# 18250_0.net
KiCad netlist of a schematic drawn in EAGLE
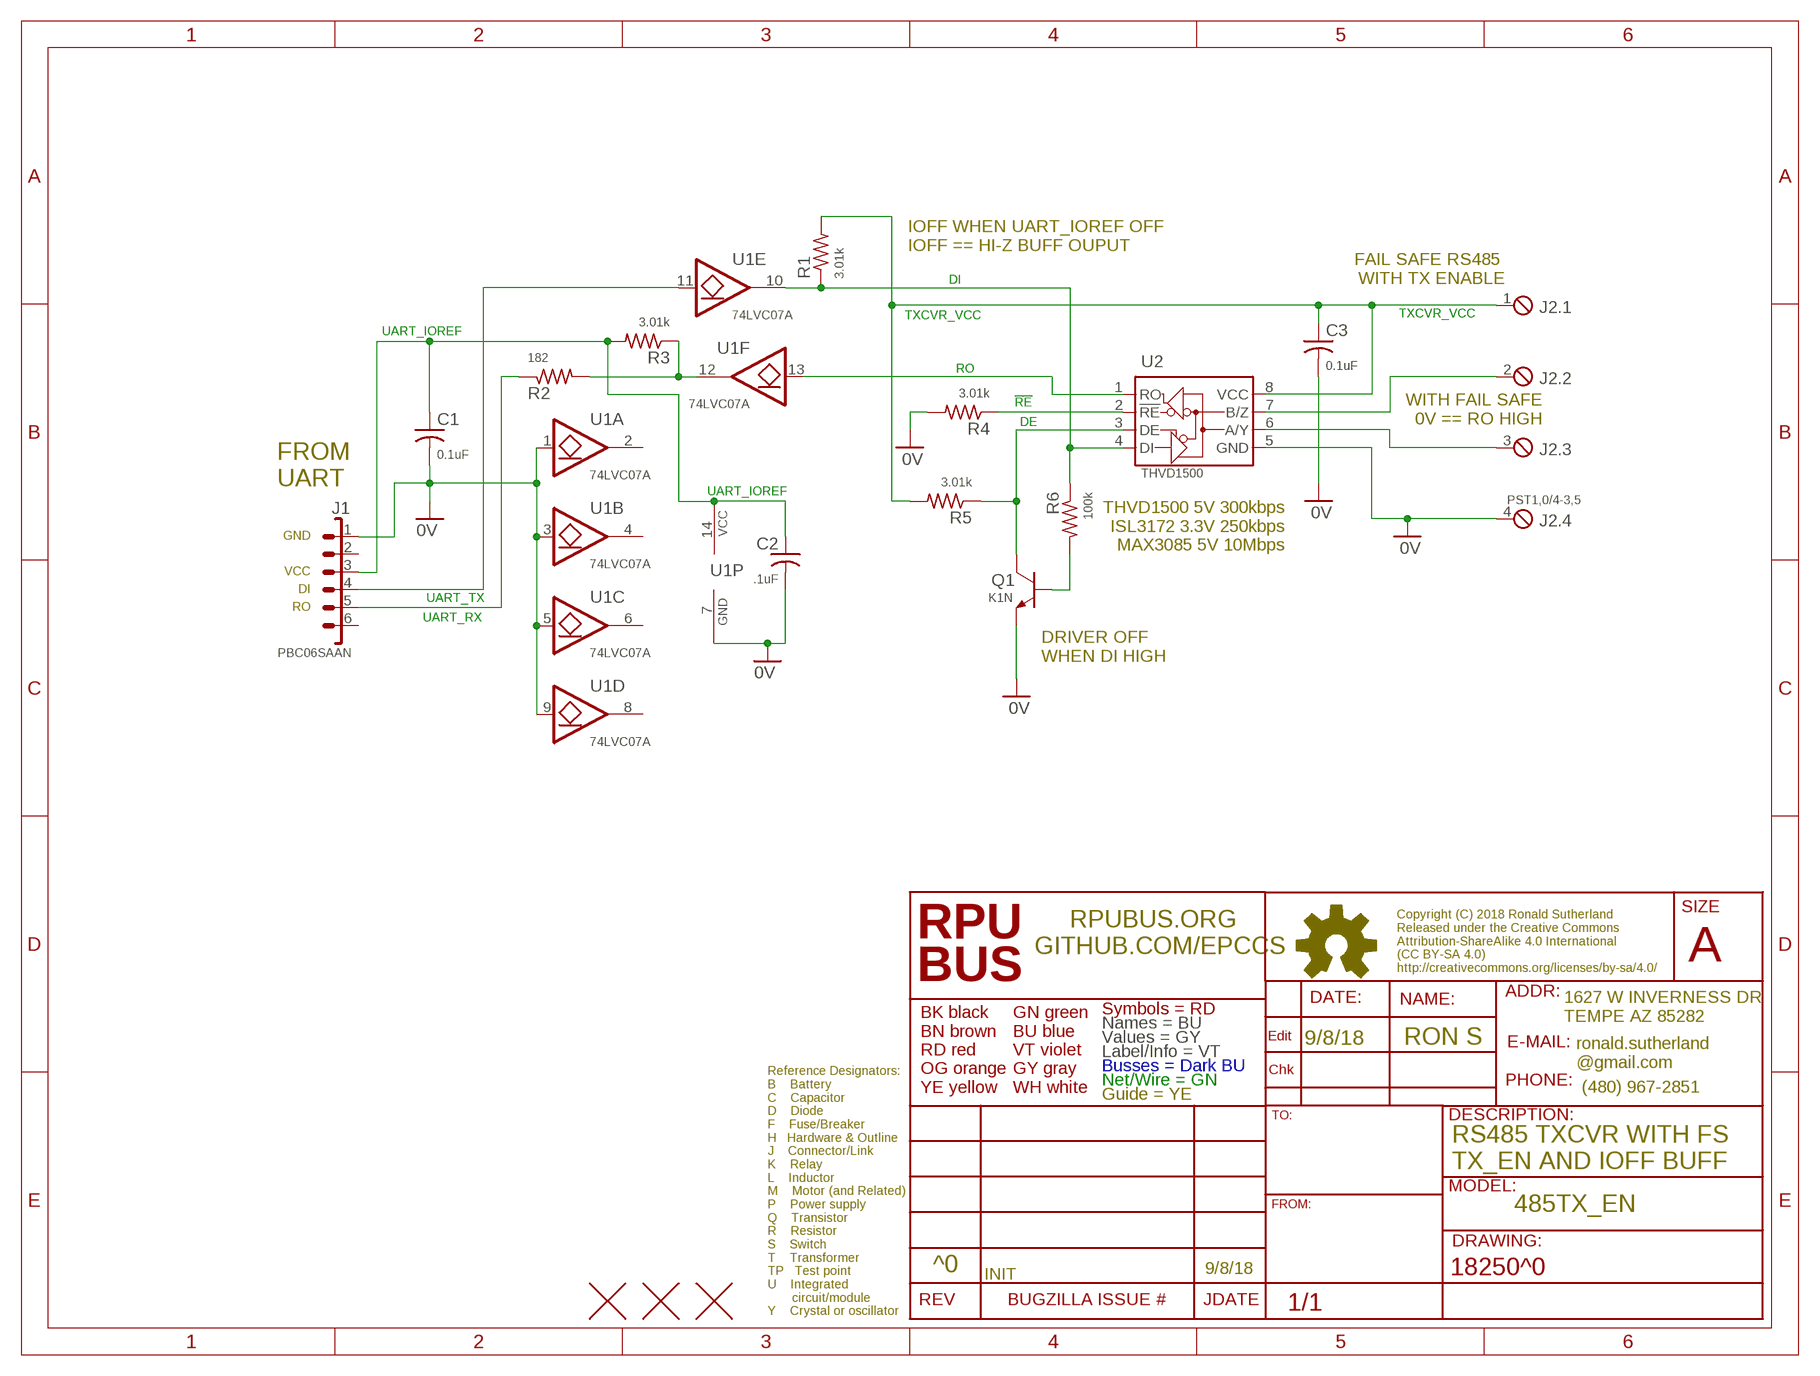
[diagram p0: schematic, sheet 1]

(export (version "E")
  (design (tool "Eeschema 10.0.6"))
  (components
    (comp (ref "C1")
      (value "0.1uF")
      (footprint "eagle-import:C0603(1608)")
      (libsource (lib "eagle-import") (part "CC0603A"))
    )
    (comp (ref "C2")
      (value ".1uF")
      (footprint "eagle-import:C0603(1608)")
      (libsource (lib "eagle-import") (part "CC0603A"))
    )
    (comp (ref "C3")
      (value "0.1uF")
      (footprint "eagle-import:C0603(1608)")
      (libsource (lib "eagle-import") (part "CC0603A"))
    )
    (comp (ref "J1")
      (value "PBC06SAAN")
      (footprint "eagle-import:1X6")
      (libsource (lib "eagle-import") (part "1X6"))
    )
    (comp (ref "J2")
      (value "PST1,0/4-3,5")
      (footprint "eagle-import:MCV4")
      (libsource (lib "eagle-import") (part "MCV4"))
    )
    (comp (ref "Q1")
      (value "K1N")
      (footprint "eagle-import:SOT23")
      (libsource (lib "eagle-import") (part "NPNSOT23"))
    )
    (comp (ref "R1")
      (value "3.01k")
      (footprint "eagle-import:C0805(2012)")
      (libsource (lib "eagle-import") (part "R0805"))
    )
    (comp (ref "R2")
      (value "182")
      (footprint "eagle-import:C0805(2012)")
      (libsource (lib "eagle-import") (part "R0805"))
    )
    (comp (ref "R3")
      (value "3.01k")
      (footprint "eagle-import:C0805(2012)")
      (libsource (lib "eagle-import") (part "R0805"))
    )
    (comp (ref "R4")
      (value "3.01k")
      (footprint "eagle-import:C0805(2012)")
      (libsource (lib "eagle-import") (part "R0805"))
    )
    (comp (ref "R5")
      (value "3.01k")
      (footprint "eagle-import:C0805(2012)")
      (libsource (lib "eagle-import") (part "R0805"))
    )
    (comp (ref "R6")
      (value "100k")
      (footprint "eagle-import:C0805(2012)")
      (libsource (lib "eagle-import") (part "R0805"))
    )
    (comp (ref "U$2")
      (value "FIDUCIAL1.27")
      (footprint "eagle-import:FIDUCIAL-1.27")
      (libsource (lib "eagle-import") (part "FIDUCIAL1.27"))
    )
    (comp (ref "U$3")
      (value "FIDUCIAL1.27")
      (footprint "eagle-import:FIDUCIAL-1.27")
      (libsource (lib "eagle-import") (part "FIDUCIAL1.27"))
    )
    (comp (ref "U$4")
      (value "FIDUCIAL1.27")
      (footprint "eagle-import:FIDUCIAL-1.27")
      (libsource (lib "eagle-import") (part "FIDUCIAL1.27"))
    )
    (comp (ref "U1")
      (value "74LVC07A")
      (footprint "eagle-import:14SOIC")
      (libsource (lib "eagle-import") (part "7407D"))
    )
    (comp (ref "U2")
      (value "THVD1500")
      (footprint "eagle-import:SOIC8")
      (libsource (lib "eagle-import") (part "ISL3172EIBZ"))
    )
  )
  (nets
    (net (code "1") (name "/DE") (class "Default")
      (node (ref "Q1") (pin "C") (pinfunction "C_C") (pintype "passive"))
      (node (ref "R5") (pin "1") (pinfunction "1_1") (pintype "passive"))
      (node (ref "U2") (pin "3") (pinfunction "DE_3") (pintype "input"))
    )
    (net (code "2") (name "/DI") (class "Default")
      (node (ref "R1") (pin "1") (pinfunction "1_1") (pintype "passive"))
      (node (ref "R6") (pin "1") (pinfunction "1_1") (pintype "passive"))
      (node (ref "U1") (pin "10") (pinfunction "O_10") (pintype "open_collector"))
      (node (ref "U2") (pin "4") (pinfunction "DI_4") (pintype "input"))
    )
    (net (code "3") (name "/RO") (class "Default")
      (node (ref "U1") (pin "13") (pinfunction "I_13") (pintype "input"))
      (node (ref "U2") (pin "1") (pinfunction "RO_1") (pintype "output"))
    )
    (net (code "4") (name "/TXCVR_VCC") (class "Default")
      (node (ref "C3") (pin "1") (pinfunction "1_1") (pintype "passive"))
      (node (ref "J2") (pin "1") (pinfunction "1_1") (pintype "passive"))
      (node (ref "R1") (pin "2") (pinfunction "2_2") (pintype "passive"))
      (node (ref "R5") (pin "2") (pinfunction "2_2") (pintype "passive"))
      (node (ref "U2") (pin "8") (pinfunction "VCC_8") (pintype "power_in"))
    )
    (net (code "5") (name "/UART_IOREF") (class "Default")
      (node (ref "C1") (pin "1") (pinfunction "1_1") (pintype "passive"))
      (node (ref "C2") (pin "1") (pinfunction "1_1") (pintype "passive"))
      (node (ref "J1") (pin "3") (pinfunction "3_3") (pintype "passive"))
      (node (ref "R3") (pin "2") (pinfunction "2_2") (pintype "passive"))
      (node (ref "U1") (pin "14") (pinfunction "VCC_14") (pintype "power_in"))
    )
    (net (code "6") (name "/UART_RX") (class "Default")
      (node (ref "J1") (pin "5") (pinfunction "5_5") (pintype "passive"))
      (node (ref "R2") (pin "1") (pinfunction "1_1") (pintype "passive"))
    )
    (net (code "7") (name "/UART_TX") (class "Default")
      (node (ref "J1") (pin "4") (pinfunction "4_4") (pintype "passive"))
      (node (ref "U1") (pin "11") (pinfunction "I_11") (pintype "input"))
    )
    (net (code "8") (name "/~{RE}") (class "Default")
      (node (ref "R4") (pin "1") (pinfunction "1_1") (pintype "passive"))
      (node (ref "U2") (pin "2") (pinfunction "~{RE}_2") (pintype "input"))
    )
    (net (code "9") (name "0V") (class "Default")
      (node (ref "C1") (pin "2") (pinfunction "2_2") (pintype "passive"))
      (node (ref "C2") (pin "2") (pinfunction "2_2") (pintype "passive"))
      (node (ref "C3") (pin "2") (pinfunction "2_2") (pintype "passive"))
      (node (ref "J1") (pin "1") (pinfunction "1_1") (pintype "passive"))
      (node (ref "J2") (pin "4") (pinfunction "1_4") (pintype "passive"))
      (node (ref "Q1") (pin "E") (pinfunction "E_E") (pintype "passive"))
      (node (ref "R4") (pin "2") (pinfunction "2_2") (pintype "passive"))
      (node (ref "U1") (pin "1") (pinfunction "I_1") (pintype "input"))
      (node (ref "U1") (pin "3") (pinfunction "I_3") (pintype "input"))
      (node (ref "U1") (pin "5") (pinfunction "I_5") (pintype "input"))
      (node (ref "U1") (pin "7") (pinfunction "GND_7") (pintype "power_in"))
      (node (ref "U1") (pin "9") (pinfunction "I_9") (pintype "input"))
      (node (ref "U2") (pin "5") (pinfunction "GND_5") (pintype "power_in"))
    )
    (net (code "10") (name "Net-(J2B-1)") (class "Default")
      (node (ref "J2") (pin "2") (pinfunction "1_2") (pintype "passive"))
      (node (ref "U2") (pin "7") (pinfunction "B/Z_7") (pintype "bidirectional"))
    )
    (net (code "11") (name "Net-(J2C-1)") (class "Default")
      (node (ref "J2") (pin "3") (pinfunction "1_3") (pintype "passive"))
      (node (ref "U2") (pin "6") (pinfunction "A/Y_6") (pintype "bidirectional"))
    )
    (net (code "12") (name "Net-(Q1-PadB)") (class "Default")
      (node (ref "Q1") (pin "B") (pinfunction "B_B") (pintype "passive"))
      (node (ref "R6") (pin "2") (pinfunction "2_2") (pintype "passive"))
    )
    (net (code "13") (name "Net-(U1F-O)") (class "Default")
      (node (ref "R2") (pin "2") (pinfunction "2_2") (pintype "passive"))
      (node (ref "R3") (pin "1") (pinfunction "1_1") (pintype "passive"))
      (node (ref "U1") (pin "12") (pinfunction "O_12") (pintype "open_collector"))
    )
    (net (code "14") (name "unconnected-(J1-Pad2)") (class "Default")
      (node (ref "J1") (pin "2") (pinfunction "2_2") (pintype "passive"))
    )
    (net (code "15") (name "unconnected-(J1-Pad6)") (class "Default")
      (node (ref "J1") (pin "6") (pinfunction "6_6") (pintype "passive"))
    )
    (net (code "16") (name "unconnected-(U1A-O-Pad2)") (class "Default")
      (node (ref "U1") (pin "2") (pinfunction "O_2") (pintype "open_collector"))
    )
    (net (code "17") (name "unconnected-(U1B-O-Pad4)") (class "Default")
      (node (ref "U1") (pin "4") (pinfunction "O_4") (pintype "open_collector"))
    )
    (net (code "18") (name "unconnected-(U1C-O-Pad6)") (class "Default")
      (node (ref "U1") (pin "6") (pinfunction "O_6") (pintype "open_collector"))
    )
    (net (code "19") (name "unconnected-(U1D-O-Pad8)") (class "Default")
      (node (ref "U1") (pin "8") (pinfunction "O_8") (pintype "open_collector"))
    )
  )
)
